# STM32.net
KiCad netlist of a schematic drawn in Altium Designer
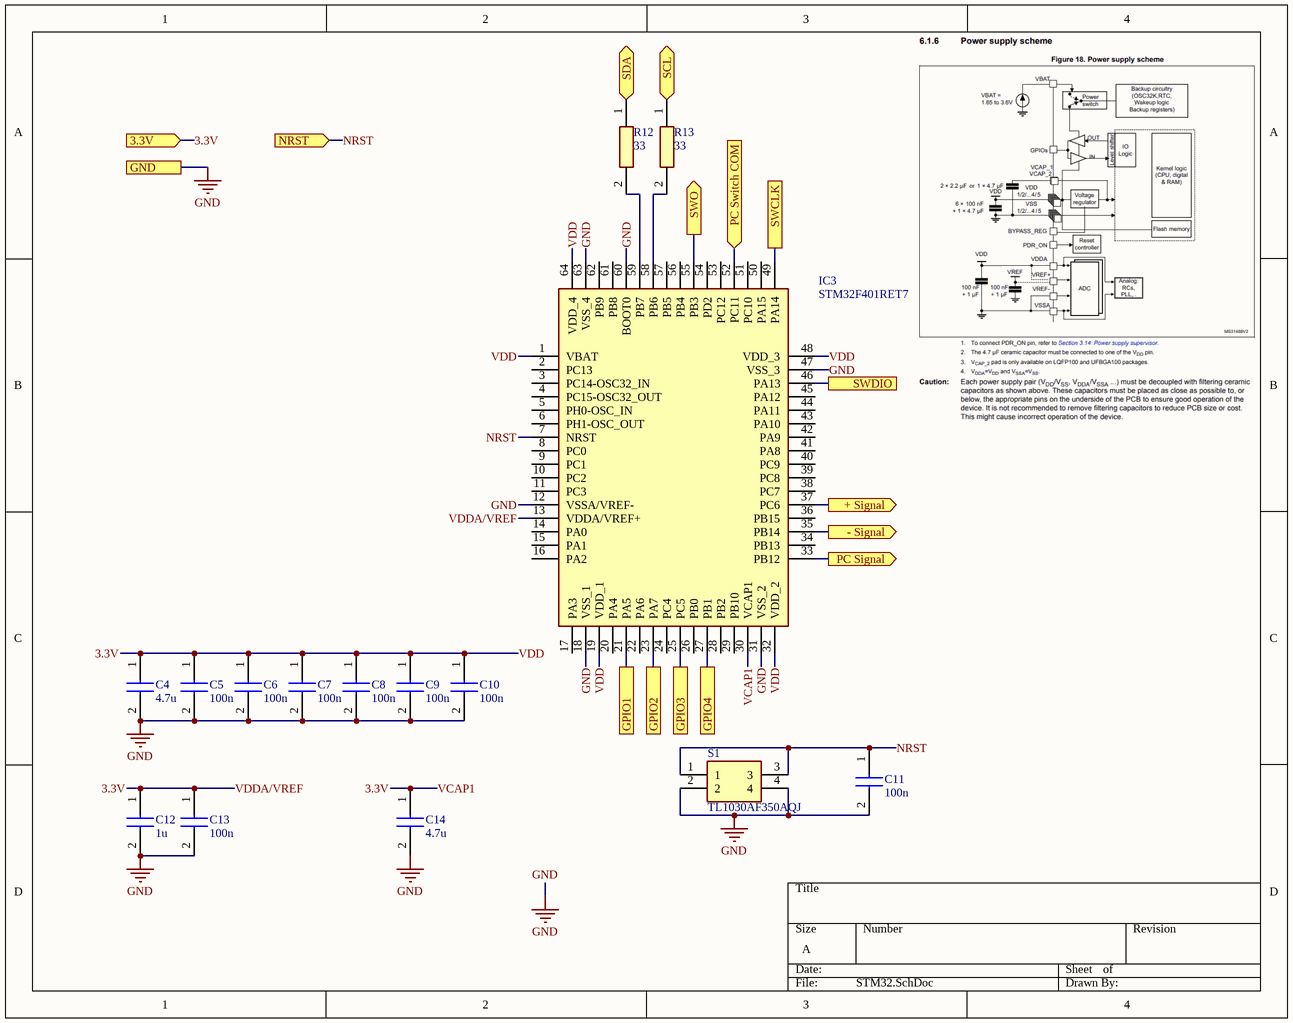
[diagram p0: STM32.SchDoc]

(export (version "E")
  (design (tool "Eeschema 10.0.6"))
  (components
    (comp (ref "C4")
      (value "4.7u")
      (footprint "SamacSys:CAPC3216X180N")
      (description "Capacitor")
      (fields
        (field (name "MANUFACTURER_PART_NUMBER") "GMK316AB7475KLHT")
        (field (name "MOUSER PART NUMBER") "963-GMK316AB7475KLHT")
      )
      (libsource (lib "SamacSys") (part "GMK316AB7475KLHT"))
    )
    (comp (ref "C5")
      (value "100n")
      (footprint "SamacSys:CAPC3216X94N")
      (description "Capacitor")
      (fields
        (field (name "MANUFACTURER_PART_NUMBER") "12065C104J4Z2A")
        (field (name "MOUSER PART NUMBER") "581-12065C104J4Z2A")
      )
      (libsource (lib "SamacSys") (part "12065C104J4Z2A"))
    )
    (comp (ref "C6")
      (value "100n")
      (footprint "SamacSys:CAPC3216X94N")
      (description "Capacitor")
      (fields
        (field (name "MANUFACTURER_PART_NUMBER") "12065C104J4Z2A")
        (field (name "MOUSER PART NUMBER") "581-12065C104J4Z2A")
      )
      (libsource (lib "SamacSys") (part "12065C104J4Z2A"))
    )
    (comp (ref "C7")
      (value "100n")
      (footprint "SamacSys:CAPC3216X94N")
      (description "Capacitor")
      (fields
        (field (name "MANUFACTURER_PART_NUMBER") "12065C104J4Z2A")
        (field (name "MOUSER PART NUMBER") "581-12065C104J4Z2A")
      )
      (libsource (lib "SamacSys") (part "12065C104J4Z2A"))
    )
    (comp (ref "C8")
      (value "100n")
      (footprint "SamacSys:CAPC3216X94N")
      (description "Capacitor")
      (fields
        (field (name "MANUFACTURER_PART_NUMBER") "12065C104J4Z2A")
        (field (name "MOUSER PART NUMBER") "581-12065C104J4Z2A")
      )
      (libsource (lib "SamacSys") (part "12065C104J4Z2A"))
    )
    (comp (ref "C9")
      (value "100n")
      (footprint "SamacSys:CAPC3216X94N")
      (description "Capacitor")
      (fields
        (field (name "MANUFACTURER_PART_NUMBER") "12065C104J4Z2A")
        (field (name "MOUSER PART NUMBER") "581-12065C104J4Z2A")
      )
      (libsource (lib "SamacSys") (part "12065C104J4Z2A"))
    )
    (comp (ref "C10")
      (value "100n")
      (footprint "SamacSys:CAPC3216X94N")
      (description "Capacitor")
      (fields
        (field (name "MANUFACTURER_PART_NUMBER") "12065C104J4Z2A")
        (field (name "MOUSER PART NUMBER") "581-12065C104J4Z2A")
      )
      (libsource (lib "SamacSys") (part "12065C104J4Z2A"))
    )
    (comp (ref "C11")
      (value "100n")
      (footprint "SamacSys:CAPC3216X94N")
      (description "Capacitor")
      (fields
        (field (name "MANUFACTURER_PART_NUMBER") "12065C104J4Z2A")
        (field (name "MOUSER PART NUMBER") "581-12065C104J4Z2A")
      )
      (libsource (lib "SamacSys") (part "12065C104J4Z2A"))
    )
    (comp (ref "C12")
      (value "1u")
      (footprint "SamacSys:CAPC3216X180N")
      (description "Capacitor")
      (fields
        (field (name "MANUFACTURER_PART_NUMBER") "HMK316B7105KLHT")
        (field (name "MOUSER PART NUMBER") "963-HMK316B7105KLHT")
      )
      (libsource (lib "SamacSys") (part "HMK316B7105KLHT"))
    )
    (comp (ref "C13")
      (value "100n")
      (footprint "SamacSys:CAPC3216X94N")
      (description "Capacitor")
      (fields
        (field (name "MANUFACTURER_PART_NUMBER") "12065C104J4Z2A")
        (field (name "MOUSER PART NUMBER") "581-12065C104J4Z2A")
      )
      (libsource (lib "SamacSys") (part "12065C104J4Z2A"))
    )
    (comp (ref "C14")
      (value "4.7u")
      (footprint "SamacSys:CAPC3216X180N")
      (description "Capacitor")
      (fields
        (field (name "MANUFACTURER_PART_NUMBER") "GMK316AB7475KLHT")
        (field (name "MOUSER PART NUMBER") "963-GMK316AB7475KLHT")
      )
      (libsource (lib "SamacSys") (part "GMK316AB7475KLHT"))
    )
    (comp (ref "IC3")
      (value "STM32F401RET7")
      (footprint "SamacSys:QFP50P1200X1200X160-64N")
      (description "Integrated Circuit")
      (fields (field (name "MOUSER PART NUMBER") "511-STM32F401RET7"))
      (libsource (lib "*") (part "STM32F401RET7"))
    )
    (comp (ref "R12")
      (value "33")
      (footprint "SamacSys:ERJ8ENF1000V")
      (description "Resistor")
      (fields
        (field (name "MANUFACTURER_PART_NUMBER") "ERJ-8ENF33R0V")
        (field (name "MOUSER PART NUMBER") "667-ERJ-8ENF33R0V")
      )
      (libsource (lib "SamacSys") (part "ERJ-8ENF33R0V"))
    )
    (comp (ref "R13")
      (value "33")
      (footprint "SamacSys:ERJ8ENF1000V")
      (description "Resistor")
      (fields
        (field (name "MANUFACTURER_PART_NUMBER") "ERJ-8ENF33R0V")
        (field (name "MOUSER PART NUMBER") "667-ERJ-8ENF33R0V")
      )
      (libsource (lib "SamacSys") (part "ERJ-8ENF33R0V"))
    )
    (comp (ref "S1")
      (value "TL1030AF350AQJ")
      (footprint "SamacSys:TL1030AF350AQJ")
      (description "Switch")
      (fields (field (name "MOUSER PART NUMBER") "612-TL1030AF350AQJ"))
      (libsource (lib "SamacSys") (part "TL1030AF350AQJ"))
    )
  )
  (nets
    (net (code "1") (name "/+ Signal") (class "Default")
      (node (ref "IC3") (pin "37") (pinfunction "PC6_37") (pintype "passive"))
    )
    (net (code "2") (name "/- Signal") (class "Default")
      (node (ref "IC3") (pin "35") (pinfunction "PB14_35") (pintype "passive"))
    )
    (net (code "3") (name "/3.3V") (class "Default")
      (node (ref "C10") (pin "1") (pinfunction "1_1") (pintype "passive"))
      (node (ref "C12") (pin "1") (pinfunction "1_1") (pintype "passive"))
      (node (ref "C13") (pin "1") (pinfunction "1_1") (pintype "passive"))
      (node (ref "C14") (pin "1") (pinfunction "1_1") (pintype "passive"))
      (node (ref "C4") (pin "1") (pinfunction "1_1") (pintype "passive"))
      (node (ref "C5") (pin "1") (pinfunction "1_1") (pintype "passive"))
      (node (ref "C6") (pin "1") (pinfunction "1_1") (pintype "passive"))
      (node (ref "C7") (pin "1") (pinfunction "1_1") (pintype "passive"))
      (node (ref "C8") (pin "1") (pinfunction "1_1") (pintype "passive"))
      (node (ref "C9") (pin "1") (pinfunction "1_1") (pintype "passive"))
      (node (ref "IC3") (pin "1") (pinfunction "VBAT_1") (pintype "passive"))
      (node (ref "IC3") (pin "13") (pinfunction "VDDA/VREF+_13") (pintype "passive"))
      (node (ref "IC3") (pin "19") (pinfunction "VDD_1_19") (pintype "passive"))
      (node (ref "IC3") (pin "30") (pinfunction "VCAP1_30") (pintype "passive"))
      (node (ref "IC3") (pin "32") (pinfunction "VDD_2_32") (pintype "passive"))
      (node (ref "IC3") (pin "48") (pinfunction "VDD_3_48") (pintype "passive"))
      (node (ref "IC3") (pin "64") (pinfunction "VDD_4_64") (pintype "passive"))
    )
    (net (code "4") (name "/GPIO1") (class "Default")
      (node (ref "IC3") (pin "21") (pinfunction "PA5_21") (pintype "passive"))
    )
    (net (code "5") (name "/GPIO2") (class "Default")
      (node (ref "IC3") (pin "23") (pinfunction "PA7_23") (pintype "passive"))
    )
    (net (code "6") (name "/GPIO3") (class "Default")
      (node (ref "IC3") (pin "25") (pinfunction "PC5_25") (pintype "passive"))
    )
    (net (code "7") (name "/GPIO4") (class "Default")
      (node (ref "IC3") (pin "27") (pinfunction "PB1_27") (pintype "passive"))
    )
    (net (code "8") (name "/NRST") (class "Default")
      (node (ref "C11") (pin "1") (pinfunction "1_1") (pintype "passive"))
      (node (ref "IC3") (pin "7") (pinfunction "NRST_7") (pintype "passive"))
      (node (ref "S1") (pin "1") (pinfunction "1_1") (pintype "passive"))
      (node (ref "S1") (pin "3") (pinfunction "3_3") (pintype "passive"))
    )
    (net (code "9") (name "/PC Signal") (class "Default")
      (node (ref "IC3") (pin "33") (pinfunction "PB12_33") (pintype "passive"))
    )
    (net (code "10") (name "/PC Switch COM") (class "Default")
      (node (ref "IC3") (pin "52") (pinfunction "PC11_52") (pintype "passive"))
    )
    (net (code "11") (name "/SCL") (class "Default")
      (node (ref "R13") (pin "1") (pinfunction "1_1") (pintype "passive"))
    )
    (net (code "12") (name "/SDA") (class "Default")
      (node (ref "R12") (pin "1") (pinfunction "1_1") (pintype "passive"))
    )
    (net (code "13") (name "/SWCLK") (class "Default")
      (node (ref "IC3") (pin "49") (pinfunction "PA14_49") (pintype "passive"))
    )
    (net (code "14") (name "/SWDIO") (class "Default")
      (node (ref "IC3") (pin "46") (pinfunction "PA13_46") (pintype "passive"))
    )
    (net (code "15") (name "/SWO") (class "Default")
      (node (ref "IC3") (pin "55") (pinfunction "PB3_55") (pintype "passive"))
    )
    (net (code "16") (name "GND") (class "Default")
      (node (ref "C10") (pin "2") (pinfunction "2_2") (pintype "passive"))
      (node (ref "C11") (pin "2") (pinfunction "2_2") (pintype "passive"))
      (node (ref "C12") (pin "2") (pinfunction "2_2") (pintype "passive"))
      (node (ref "C13") (pin "2") (pinfunction "2_2") (pintype "passive"))
      (node (ref "C14") (pin "2") (pinfunction "2_2") (pintype "passive"))
      (node (ref "C4") (pin "2") (pinfunction "2_2") (pintype "passive"))
      (node (ref "C5") (pin "2") (pinfunction "2_2") (pintype "passive"))
      (node (ref "C6") (pin "2") (pinfunction "2_2") (pintype "passive"))
      (node (ref "C7") (pin "2") (pinfunction "2_2") (pintype "passive"))
      (node (ref "C8") (pin "2") (pinfunction "2_2") (pintype "passive"))
      (node (ref "C9") (pin "2") (pinfunction "2_2") (pintype "passive"))
      (node (ref "IC3") (pin "12") (pinfunction "VSSA/VREF-_12") (pintype "passive"))
      (node (ref "IC3") (pin "18") (pinfunction "VSS_1_18") (pintype "passive"))
      (node (ref "IC3") (pin "31") (pinfunction "VSS_2_31") (pintype "passive"))
      (node (ref "IC3") (pin "47") (pinfunction "VSS_3_47") (pintype "passive"))
      (node (ref "IC3") (pin "60") (pinfunction "BOOT0_60") (pintype "passive"))
      (node (ref "IC3") (pin "63") (pinfunction "VSS_4_63") (pintype "passive"))
      (node (ref "S1") (pin "2") (pinfunction "2_2") (pintype "passive"))
      (node (ref "S1") (pin "4") (pinfunction "4_4") (pintype "passive"))
    )
    (net (code "17") (name "Net-(IC3-PB6)") (class "Default")
      (node (ref "IC3") (pin "58") (pinfunction "PB6_58") (pintype "passive"))
      (node (ref "R13") (pin "2") (pinfunction "2_2") (pintype "passive"))
    )
    (net (code "18") (name "Net-(IC3-PB7)") (class "Default")
      (node (ref "IC3") (pin "59") (pinfunction "PB7_59") (pintype "passive"))
      (node (ref "R12") (pin "2") (pinfunction "2_2") (pintype "passive"))
    )
    (net (code "19") (name "unconnected-(IC3-PA0-Pad14)") (class "Default")
      (node (ref "IC3") (pin "14") (pinfunction "PA0_14") (pintype "passive"))
    )
    (net (code "20") (name "unconnected-(IC3-PA1-Pad15)") (class "Default")
      (node (ref "IC3") (pin "15") (pinfunction "PA1_15") (pintype "passive"))
    )
    (net (code "21") (name "unconnected-(IC3-PA2-Pad16)") (class "Default")
      (node (ref "IC3") (pin "16") (pinfunction "PA2_16") (pintype "passive"))
    )
    (net (code "22") (name "unconnected-(IC3-PA3-Pad17)") (class "Default")
      (node (ref "IC3") (pin "17") (pinfunction "PA3_17") (pintype "passive"))
    )
    (net (code "23") (name "unconnected-(IC3-PA4-Pad20)") (class "Default")
      (node (ref "IC3") (pin "20") (pinfunction "PA4_20") (pintype "passive"))
    )
    (net (code "24") (name "unconnected-(IC3-PA6-Pad22)") (class "Default")
      (node (ref "IC3") (pin "22") (pinfunction "PA6_22") (pintype "passive"))
    )
    (net (code "25") (name "unconnected-(IC3-PA8-Pad41)") (class "Default")
      (node (ref "IC3") (pin "41") (pinfunction "PA8_41") (pintype "passive"))
    )
    (net (code "26") (name "unconnected-(IC3-PA9-Pad42)") (class "Default")
      (node (ref "IC3") (pin "42") (pinfunction "PA9_42") (pintype "passive"))
    )
    (net (code "27") (name "unconnected-(IC3-PA10-Pad43)") (class "Default")
      (node (ref "IC3") (pin "43") (pinfunction "PA10_43") (pintype "passive"))
    )
    (net (code "28") (name "unconnected-(IC3-PA11-Pad44)") (class "Default")
      (node (ref "IC3") (pin "44") (pinfunction "PA11_44") (pintype "passive"))
    )
    (net (code "29") (name "unconnected-(IC3-PA12-Pad45)") (class "Default")
      (node (ref "IC3") (pin "45") (pinfunction "PA12_45") (pintype "passive"))
    )
    (net (code "30") (name "unconnected-(IC3-PA15-Pad50)") (class "Default")
      (node (ref "IC3") (pin "50") (pinfunction "PA15_50") (pintype "passive"))
    )
    (net (code "31") (name "unconnected-(IC3-PB0-Pad26)") (class "Default")
      (node (ref "IC3") (pin "26") (pinfunction "PB0_26") (pintype "passive"))
    )
    (net (code "32") (name "unconnected-(IC3-PB2-Pad28)") (class "Default")
      (node (ref "IC3") (pin "28") (pinfunction "PB2_28") (pintype "passive"))
    )
    (net (code "33") (name "unconnected-(IC3-PB4-Pad56)") (class "Default")
      (node (ref "IC3") (pin "56") (pinfunction "PB4_56") (pintype "passive"))
    )
    (net (code "34") (name "unconnected-(IC3-PB5-Pad57)") (class "Default")
      (node (ref "IC3") (pin "57") (pinfunction "PB5_57") (pintype "passive"))
    )
    (net (code "35") (name "unconnected-(IC3-PB8-Pad61)") (class "Default")
      (node (ref "IC3") (pin "61") (pinfunction "PB8_61") (pintype "passive"))
    )
    (net (code "36") (name "unconnected-(IC3-PB9-Pad62)") (class "Default")
      (node (ref "IC3") (pin "62") (pinfunction "PB9_62") (pintype "passive"))
    )
    (net (code "37") (name "unconnected-(IC3-PB10-Pad29)") (class "Default")
      (node (ref "IC3") (pin "29") (pinfunction "PB10_29") (pintype "passive"))
    )
    (net (code "38") (name "unconnected-(IC3-PB13-Pad34)") (class "Default")
      (node (ref "IC3") (pin "34") (pinfunction "PB13_34") (pintype "passive"))
    )
    (net (code "39") (name "unconnected-(IC3-PB15-Pad36)") (class "Default")
      (node (ref "IC3") (pin "36") (pinfunction "PB15_36") (pintype "passive"))
    )
    (net (code "40") (name "unconnected-(IC3-PC0-Pad8)") (class "Default")
      (node (ref "IC3") (pin "8") (pinfunction "PC0_8") (pintype "passive"))
    )
    (net (code "41") (name "unconnected-(IC3-PC1-Pad9)") (class "Default")
      (node (ref "IC3") (pin "9") (pinfunction "PC1_9") (pintype "passive"))
    )
    (net (code "42") (name "unconnected-(IC3-PC2-Pad10)") (class "Default")
      (node (ref "IC3") (pin "10") (pinfunction "PC2_10") (pintype "passive"))
    )
    (net (code "43") (name "unconnected-(IC3-PC3-Pad11)") (class "Default")
      (node (ref "IC3") (pin "11") (pinfunction "PC3_11") (pintype "passive"))
    )
    (net (code "44") (name "unconnected-(IC3-PC4-Pad24)") (class "Default")
      (node (ref "IC3") (pin "24") (pinfunction "PC4_24") (pintype "passive"))
    )
    (net (code "45") (name "unconnected-(IC3-PC7-Pad38)") (class "Default")
      (node (ref "IC3") (pin "38") (pinfunction "PC7_38") (pintype "passive"))
    )
    (net (code "46") (name "unconnected-(IC3-PC8-Pad39)") (class "Default")
      (node (ref "IC3") (pin "39") (pinfunction "PC8_39") (pintype "passive"))
    )
    (net (code "47") (name "unconnected-(IC3-PC9-Pad40)") (class "Default")
      (node (ref "IC3") (pin "40") (pinfunction "PC9_40") (pintype "passive"))
    )
    (net (code "48") (name "unconnected-(IC3-PC10-Pad51)") (class "Default")
      (node (ref "IC3") (pin "51") (pinfunction "PC10_51") (pintype "passive"))
    )
    (net (code "49") (name "unconnected-(IC3-PC12-Pad53)") (class "Default")
      (node (ref "IC3") (pin "53") (pinfunction "PC12_53") (pintype "passive"))
    )
    (net (code "50") (name "unconnected-(IC3-PC13-Pad2)") (class "Default")
      (node (ref "IC3") (pin "2") (pinfunction "PC13_2") (pintype "passive"))
    )
    (net (code "51") (name "unconnected-(IC3-PC14-OSC32_IN-Pad3)") (class "Default")
      (node (ref "IC3") (pin "3") (pinfunction "PC14-OSC32_IN_3") (pintype "passive"))
    )
    (net (code "52") (name "unconnected-(IC3-PC15-OSC32_OUT-Pad4)") (class "Default")
      (node (ref "IC3") (pin "4") (pinfunction "PC15-OSC32_OUT_4") (pintype "passive"))
    )
    (net (code "53") (name "unconnected-(IC3-PD2-Pad54)") (class "Default")
      (node (ref "IC3") (pin "54") (pinfunction "PD2_54") (pintype "passive"))
    )
    (net (code "54") (name "unconnected-(IC3-PH0-OSC_IN-Pad5)") (class "Default")
      (node (ref "IC3") (pin "5") (pinfunction "PH0-OSC_IN_5") (pintype "passive"))
    )
    (net (code "55") (name "unconnected-(IC3-PH1-OSC_OUT-Pad6)") (class "Default")
      (node (ref "IC3") (pin "6") (pinfunction "PH1-OSC_OUT_6") (pintype "passive"))
    )
  )
)
